# Longan_Nano_SIL_Adapter.net
KiCad netlist of a schematic drawn in EAGLE
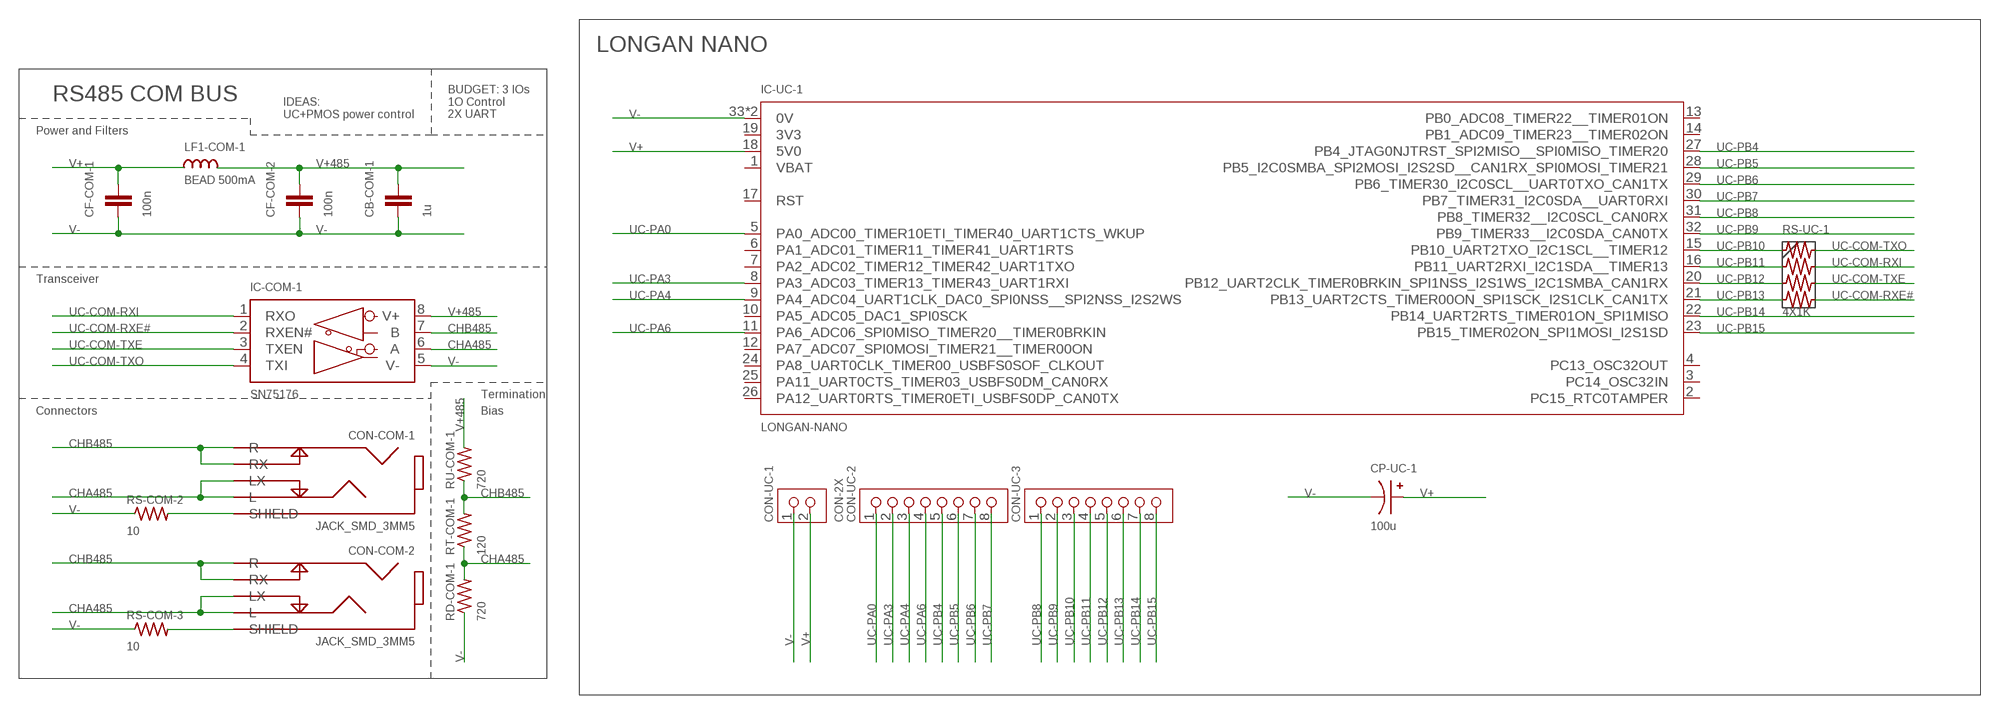
[diagram p0: schematic, sheet 1]

(export (version "E")
  (design (tool "Eeschema 10.0.6"))
  (components
    (comp (ref "CB-COM-1")
      (value "1u")
      (footprint "eagle-import:SMD-M2012")
      (libsource (lib "eagle-import") (part "C-M2012"))
    )
    (comp (ref "CF-COM-1")
      (value "100n")
      (footprint "eagle-import:SMD-M2012")
      (libsource (lib "eagle-import") (part "C-M2012"))
    )
    (comp (ref "CF-COM-2")
      (value "100n")
      (footprint "eagle-import:SMD-M2012")
      (libsource (lib "eagle-import") (part "C-M2012"))
    )
    (comp (ref "CON-COM-1")
      (value "JACK_SMD_3MM5")
      (footprint "eagle-import:JACK_SMD_3MM5")
      (libsource (lib "eagle-import") (part "JACK_SMD_3MM5"))
    )
    (comp (ref "CON-COM-2")
      (value "JACK_SMD_3MM5")
      (footprint "eagle-import:JACK_SMD_3MM5")
      (libsource (lib "eagle-import") (part "JACK_SMD_3MM5"))
    )
    (comp (ref "CON-UC-1")
      (value "CON-2X")
      (footprint "eagle-import:TH-2X2.54")
      (libsource (lib "eagle-import") (part "CON-2X"))
    )
    (comp (ref "CON-UC-2")
      (value "CON-8X")
      (footprint "eagle-import:TH-8X2.54")
      (libsource (lib "eagle-import") (part "CON-8X"))
    )
    (comp (ref "CON-UC-3")
      (value "CON-8X")
      (footprint "eagle-import:TH-8X2.54")
      (libsource (lib "eagle-import") (part "CON-8X"))
    )
    (comp (ref "CP-UC-1")
      (value "100u")
      (footprint "eagle-import:TH-BARREL-2M54-6M0")
      (libsource (lib "eagle-import") (part "C+-TH2.54-6.0"))
    )
    (comp (ref "IC-COM-1")
      (value "SN75176")
      (footprint "eagle-import:DIL08")
      (fields (field (name "MPN") "MAX481CPA+"))
      (libsource (lib "eagle-import") (part "RS485"))
    )
    (comp (ref "IC-UC-1")
      (value "LONGAN-NANO")
      (footprint "eagle-import:LONGAN-NANO")
      (libsource (lib "eagle-import") (part "LONGAN-NANO"))
    )
    (comp (ref "LF1-COM-1")
      (value "BEAD 500mA")
      (footprint "eagle-import:SMD-M2012")
      (libsource (lib "eagle-import") (part "L-M2012"))
    )
    (comp (ref "RD-COM-1")
      (value "720")
      (footprint "eagle-import:SMD-M2012")
      (libsource (lib "eagle-import") (part "R-M2012"))
    )
    (comp (ref "RS-COM-2")
      (value "10")
      (footprint "eagle-import:SMD-M2012")
      (libsource (lib "eagle-import") (part "R-M2012"))
    )
    (comp (ref "RS-COM-3")
      (value "10")
      (footprint "eagle-import:SMD-M2012")
      (libsource (lib "eagle-import") (part "R-M2012"))
    )
    (comp (ref "RS-UC-1")
      (value "4X1K")
      (footprint "eagle-import:SMD-M2012-X4")
      (libsource (lib "eagle-import") (part "RX4-M2012-X4"))
    )
    (comp (ref "RT-COM-1")
      (value "120")
      (footprint "eagle-import:TH-LINE-2M54-3M0")
      (libsource (lib "eagle-import") (part "R-V2.54-3.0"))
    )
    (comp (ref "RU-COM-1")
      (value "720")
      (footprint "eagle-import:SMD-M2012")
      (libsource (lib "eagle-import") (part "R-M2012"))
    )
  )
  (nets
    (net (code "1") (name "/3V3") (class "Default")
      (node (ref "IC-UC-1") (pin "19") (pinfunction "3V3_19") (pintype "power_in"))
    )
    (net (code "2") (name "/CHA485") (class "Default")
      (node (ref "CON-COM-1") (pin "L") (pinfunction "L_L") (pintype "bidirectional"))
      (node (ref "CON-COM-1") (pin "LX") (pinfunction "LX_LX") (pintype "bidirectional"))
      (node (ref "CON-COM-2") (pin "L") (pinfunction "L_L") (pintype "bidirectional"))
      (node (ref "CON-COM-2") (pin "LX") (pinfunction "LX_LX") (pintype "bidirectional"))
      (node (ref "IC-COM-1") (pin "6") (pinfunction "A_6") (pintype "passive"))
      (node (ref "RD-COM-1") (pin "2") (pinfunction "2_2") (pintype "passive"))
      (node (ref "RT-COM-1") (pin "P$1") (pinfunction "1_P$1") (pintype "passive"))
    )
    (net (code "3") (name "/CHB485") (class "Default")
      (node (ref "CON-COM-1") (pin "R") (pinfunction "R_R") (pintype "bidirectional"))
      (node (ref "CON-COM-1") (pin "RX") (pinfunction "RX_RX") (pintype "bidirectional"))
      (node (ref "CON-COM-2") (pin "R") (pinfunction "R_R") (pintype "bidirectional"))
      (node (ref "CON-COM-2") (pin "RX") (pinfunction "RX_RX") (pintype "bidirectional"))
      (node (ref "IC-COM-1") (pin "7") (pinfunction "B_7") (pintype "passive"))
      (node (ref "RT-COM-1") (pin "P$2") (pinfunction "2_P$2") (pintype "passive"))
      (node (ref "RU-COM-1") (pin "1") (pinfunction "1_1") (pintype "passive"))
    )
    (net (code "4") (name "/UC-COM-RXE#") (class "Default")
      (node (ref "IC-COM-1") (pin "2") (pinfunction "RXEN#_2") (pintype "input"))
      (node (ref "RS-UC-1") (pin "4B") (pinfunction "4B_4B") (pintype "bidirectional"))
    )
    (net (code "5") (name "/UC-COM-RXI") (class "Default")
      (node (ref "IC-COM-1") (pin "1") (pinfunction "RXO_1") (pintype "output"))
      (node (ref "RS-UC-1") (pin "2B") (pinfunction "2B_2B") (pintype "bidirectional"))
    )
    (net (code "6") (name "/UC-COM-TXE") (class "Default")
      (node (ref "IC-COM-1") (pin "3") (pinfunction "TXEN_3") (pintype "input"))
      (node (ref "RS-UC-1") (pin "3B") (pinfunction "3B_3B") (pintype "bidirectional"))
    )
    (net (code "7") (name "/UC-COM-TXO") (class "Default")
      (node (ref "IC-COM-1") (pin "4") (pinfunction "TXI_4") (pintype "input"))
      (node (ref "RS-UC-1") (pin "1B") (pinfunction "1B_1B") (pintype "bidirectional"))
    )
    (net (code "8") (name "/UC-PA0") (class "Default")
      (node (ref "CON-UC-2") (pin "1") (pinfunction "1_1") (pintype "passive"))
      (node (ref "IC-UC-1") (pin "5") (pinfunction "PA0_ADC00_TIMER10ETI_TIMER40_UART1CTS_WKUP_5") (pintype "bidirectional"))
    )
    (net (code "9") (name "/UC-PA3") (class "Default")
      (node (ref "CON-UC-2") (pin "2") (pinfunction "2_2") (pintype "passive"))
      (node (ref "IC-UC-1") (pin "8") (pinfunction "PA3_ADC03_TIMER13_TIMER43_UART1RXI_8") (pintype "bidirectional"))
    )
    (net (code "10") (name "/UC-PA4") (class "Default")
      (node (ref "CON-UC-2") (pin "3") (pinfunction "3_3") (pintype "passive"))
      (node (ref "IC-UC-1") (pin "9") (pinfunction "PA4_ADC04_UART1CLK_DAC0_SPI0NSS__SPI2NSS_I2S2WS_9") (pintype "bidirectional"))
    )
    (net (code "11") (name "/UC-PA6") (class "Default")
      (node (ref "CON-UC-2") (pin "4") (pinfunction "4_4") (pintype "passive"))
      (node (ref "IC-UC-1") (pin "11") (pinfunction "PA6_ADC06_SPI0MISO_TIMER20__TIMER0BRKIN_11") (pintype "bidirectional"))
    )
    (net (code "12") (name "/UC-PB4") (class "Default")
      (node (ref "CON-UC-2") (pin "5") (pinfunction "5_5") (pintype "passive"))
      (node (ref "IC-UC-1") (pin "27") (pinfunction "PB4_JTAG0NJTRST_SPI2MISO__SPI0MISO_TIMER20_27") (pintype "bidirectional"))
    )
    (net (code "13") (name "/UC-PB5") (class "Default")
      (node (ref "CON-UC-2") (pin "6") (pinfunction "6_6") (pintype "passive"))
      (node (ref "IC-UC-1") (pin "28") (pinfunction "PB5_I2C0SMBA_SPI2MOSI_I2S2SD__CAN1RX_SPI0MOSI_TIMER21_28") (pintype "bidirectional"))
    )
    (net (code "14") (name "/UC-PB6") (class "Default")
      (node (ref "CON-UC-2") (pin "7") (pinfunction "7_7") (pintype "passive"))
      (node (ref "IC-UC-1") (pin "29") (pinfunction "PB6_TIMER30_I2C0SCL__UART0TXO_CAN1TX_29") (pintype "bidirectional"))
    )
    (net (code "15") (name "/UC-PB7") (class "Default")
      (node (ref "CON-UC-2") (pin "8") (pinfunction "8_8") (pintype "passive"))
      (node (ref "IC-UC-1") (pin "30") (pinfunction "PB7_TIMER31_I2C0SDA__UART0RXI_30") (pintype "bidirectional"))
    )
    (net (code "16") (name "/UC-PB8") (class "Default")
      (node (ref "CON-UC-3") (pin "1") (pinfunction "1_1") (pintype "passive"))
      (node (ref "IC-UC-1") (pin "31") (pinfunction "PB8_TIMER32__I2C0SCL_CAN0RX_31") (pintype "bidirectional"))
    )
    (net (code "17") (name "/UC-PB9") (class "Default")
      (node (ref "CON-UC-3") (pin "2") (pinfunction "2_2") (pintype "passive"))
      (node (ref "IC-UC-1") (pin "32") (pinfunction "PB9_TIMER33__I2C0SDA_CAN0TX_32") (pintype "bidirectional"))
    )
    (net (code "18") (name "/UC-PB10") (class "Default")
      (node (ref "CON-UC-3") (pin "3") (pinfunction "3_3") (pintype "passive"))
      (node (ref "IC-UC-1") (pin "15") (pinfunction "PB10_UART2TXO_I2C1SCL__TIMER12_15") (pintype "bidirectional"))
      (node (ref "RS-UC-1") (pin "1A") (pinfunction "1A_1A") (pintype "bidirectional"))
    )
    (net (code "19") (name "/UC-PB11") (class "Default")
      (node (ref "CON-UC-3") (pin "4") (pinfunction "4_4") (pintype "passive"))
      (node (ref "IC-UC-1") (pin "16") (pinfunction "PB11_UART2RXI_I2C1SDA__TIMER13_16") (pintype "bidirectional"))
      (node (ref "RS-UC-1") (pin "2A") (pinfunction "2A_2A") (pintype "bidirectional"))
    )
    (net (code "20") (name "/UC-PB12") (class "Default")
      (node (ref "CON-UC-3") (pin "5") (pinfunction "5_5") (pintype "passive"))
      (node (ref "IC-UC-1") (pin "20") (pinfunction "PB12_UART2CLK_TIMER0BRKIN_SPI1NSS_I2S1WS_I2C1SMBA_CAN1RX_20") (pintype "bidirectional"))
      (node (ref "RS-UC-1") (pin "3A") (pinfunction "3A_3A") (pintype "bidirectional"))
    )
    (net (code "21") (name "/UC-PB13") (class "Default")
      (node (ref "CON-UC-3") (pin "6") (pinfunction "6_6") (pintype "passive"))
      (node (ref "IC-UC-1") (pin "21") (pinfunction "PB13_UART2CTS_TIMER00ON_SPI1SCK_I2S1CLK_CAN1TX_21") (pintype "bidirectional"))
      (node (ref "RS-UC-1") (pin "4A") (pinfunction "4A_4A") (pintype "bidirectional"))
    )
    (net (code "22") (name "/UC-PB14") (class "Default")
      (node (ref "CON-UC-3") (pin "7") (pinfunction "7_7") (pintype "passive"))
      (node (ref "IC-UC-1") (pin "22") (pinfunction "PB14_UART2RTS_TIMER01ON_SPI1MISO_22") (pintype "bidirectional"))
    )
    (net (code "23") (name "/UC-PB15") (class "Default")
      (node (ref "CON-UC-3") (pin "8") (pinfunction "8_8") (pintype "passive"))
      (node (ref "IC-UC-1") (pin "23") (pinfunction "PB15_TIMER02ON_SPI1MOSI_I2S1SD_23") (pintype "bidirectional"))
    )
    (net (code "24") (name "/V+") (class "Default")
      (node (ref "CF-COM-1") (pin "2") (pinfunction "2_2") (pintype "passive"))
      (node (ref "CON-UC-1") (pin "2") (pinfunction "2_2") (pintype "passive"))
      (node (ref "CP-UC-1") (pin "+") (pinfunction "+_+") (pintype "passive"))
      (node (ref "IC-UC-1") (pin "18") (pinfunction "5V0_18") (pintype "power_in"))
      (node (ref "LF1-COM-1") (pin "1") (pinfunction "1_1") (pintype "passive"))
    )
    (net (code "25") (name "/V+485") (class "Default")
      (node (ref "CB-COM-1") (pin "2") (pinfunction "2_2") (pintype "passive"))
      (node (ref "CF-COM-2") (pin "2") (pinfunction "2_2") (pintype "passive"))
      (node (ref "IC-COM-1") (pin "8") (pinfunction "V+_8") (pintype "bidirectional"))
      (node (ref "LF1-COM-1") (pin "2") (pinfunction "2_2") (pintype "passive"))
      (node (ref "RU-COM-1") (pin "2") (pinfunction "2_2") (pintype "passive"))
    )
    (net (code "26") (name "/V-") (class "Default")
      (node (ref "CB-COM-1") (pin "1") (pinfunction "1_1") (pintype "passive"))
      (node (ref "CF-COM-1") (pin "1") (pinfunction "1_1") (pintype "passive"))
      (node (ref "CF-COM-2") (pin "1") (pinfunction "1_1") (pintype "passive"))
      (node (ref "CON-UC-1") (pin "1") (pinfunction "1_1") (pintype "passive"))
      (node (ref "CP-UC-1") (pin "-") (pinfunction "-_-") (pintype "passive"))
      (node (ref "IC-COM-1") (pin "5") (pinfunction "V-_5") (pintype "bidirectional"))
      (node (ref "IC-UC-1") (pin "33") (pinfunction "0V_33") (pintype "power_in"))
      (node (ref "IC-UC-1") (pin "34") (pinfunction "0V_34") (pintype "power_in"))
      (node (ref "RD-COM-1") (pin "1") (pinfunction "1_1") (pintype "passive"))
      (node (ref "RS-COM-2") (pin "1") (pinfunction "1_1") (pintype "passive"))
      (node (ref "RS-COM-3") (pin "1") (pinfunction "1_1") (pintype "passive"))
    )
    (net (code "27") (name "/VBAT") (class "Default")
      (node (ref "IC-UC-1") (pin "1") (pinfunction "VBAT_1") (pintype "power_in"))
    )
    (net (code "28") (name "Net-(CON-COM-1-PadSHIELD)") (class "Default")
      (node (ref "CON-COM-1") (pin "SHIELD") (pinfunction "SHIELD_SHIELD") (pintype "bidirectional"))
      (node (ref "RS-COM-2") (pin "2") (pinfunction "2_2") (pintype "passive"))
    )
    (net (code "29") (name "Net-(CON-COM-2-PadSHIELD)") (class "Default")
      (node (ref "CON-COM-2") (pin "SHIELD") (pinfunction "SHIELD_SHIELD") (pintype "bidirectional"))
      (node (ref "RS-COM-3") (pin "2") (pinfunction "2_2") (pintype "passive"))
    )
    (net (code "30") (name "unconnected-(IC-UC-1-PA1_ADC01_TIMER11_TIMER41_UART1RTS-Pad6)") (class "Default")
      (node (ref "IC-UC-1") (pin "6") (pinfunction "PA1_ADC01_TIMER11_TIMER41_UART1RTS_6") (pintype "bidirectional"))
    )
    (net (code "31") (name "unconnected-(IC-UC-1-PA2_ADC02_TIMER12_TIMER42_UART1TXO-Pad7)") (class "Default")
      (node (ref "IC-UC-1") (pin "7") (pinfunction "PA2_ADC02_TIMER12_TIMER42_UART1TXO_7") (pintype "bidirectional"))
    )
    (net (code "32") (name "unconnected-(IC-UC-1-PA5_ADC05_DAC1_SPI0SCK-Pad10)") (class "Default")
      (node (ref "IC-UC-1") (pin "10") (pinfunction "PA5_ADC05_DAC1_SPI0SCK_10") (pintype "bidirectional"))
    )
    (net (code "33") (name "unconnected-(IC-UC-1-PA7_ADC07_SPI0MOSI_TIMER21__TIMER00ON-Pad12)") (class "Default")
      (node (ref "IC-UC-1") (pin "12") (pinfunction "PA7_ADC07_SPI0MOSI_TIMER21__TIMER00ON_12") (pintype "bidirectional"))
    )
    (net (code "34") (name "unconnected-(IC-UC-1-PA8_UART0CLK_TIMER00_USBFS0SOF_CLKOUT-Pad24)") (class "Default")
      (node (ref "IC-UC-1") (pin "24") (pinfunction "PA8_UART0CLK_TIMER00_USBFS0SOF_CLKOUT_24") (pintype "bidirectional"))
    )
    (net (code "35") (name "unconnected-(IC-UC-1-PA11_UART0CTS_TIMER03_USBFS0DM_CAN0RX-Pad25)") (class "Default")
      (node (ref "IC-UC-1") (pin "25") (pinfunction "PA11_UART0CTS_TIMER03_USBFS0DM_CAN0RX_25") (pintype "bidirectional"))
    )
    (net (code "36") (name "unconnected-(IC-UC-1-PA12_UART0RTS_TIMER0ETI_USBFS0DP_CAN0TX-Pad26)") (class "Default")
      (node (ref "IC-UC-1") (pin "26") (pinfunction "PA12_UART0RTS_TIMER0ETI_USBFS0DP_CAN0TX_26") (pintype "bidirectional"))
    )
    (net (code "37") (name "unconnected-(IC-UC-1-PB0_ADC08_TIMER22__TIMER01ON-Pad13)") (class "Default")
      (node (ref "IC-UC-1") (pin "13") (pinfunction "PB0_ADC08_TIMER22__TIMER01ON_13") (pintype "bidirectional"))
    )
    (net (code "38") (name "unconnected-(IC-UC-1-PB1_ADC09_TIMER23__TIMER02ON-Pad14)") (class "Default")
      (node (ref "IC-UC-1") (pin "14") (pinfunction "PB1_ADC09_TIMER23__TIMER02ON_14") (pintype "bidirectional"))
    )
    (net (code "39") (name "unconnected-(IC-UC-1-PC13_OSC32OUT-Pad4)") (class "Default")
      (node (ref "IC-UC-1") (pin "4") (pinfunction "PC13_OSC32OUT_4") (pintype "bidirectional"))
    )
    (net (code "40") (name "unconnected-(IC-UC-1-PC14_OSC32IN-Pad3)") (class "Default")
      (node (ref "IC-UC-1") (pin "3") (pinfunction "PC14_OSC32IN_3") (pintype "bidirectional"))
    )
    (net (code "41") (name "unconnected-(IC-UC-1-PC15_RTC0TAMPER-Pad2)") (class "Default")
      (node (ref "IC-UC-1") (pin "2") (pinfunction "PC15_RTC0TAMPER_2") (pintype "bidirectional"))
    )
    (net (code "42") (name "unconnected-(IC-UC-1-RST-Pad17)") (class "Default")
      (node (ref "IC-UC-1") (pin "17") (pinfunction "RST_17") (pintype "bidirectional"))
    )
  )
)
